# Messgeraet.net
KiCad netlist of a schematic drawn in EAGLE
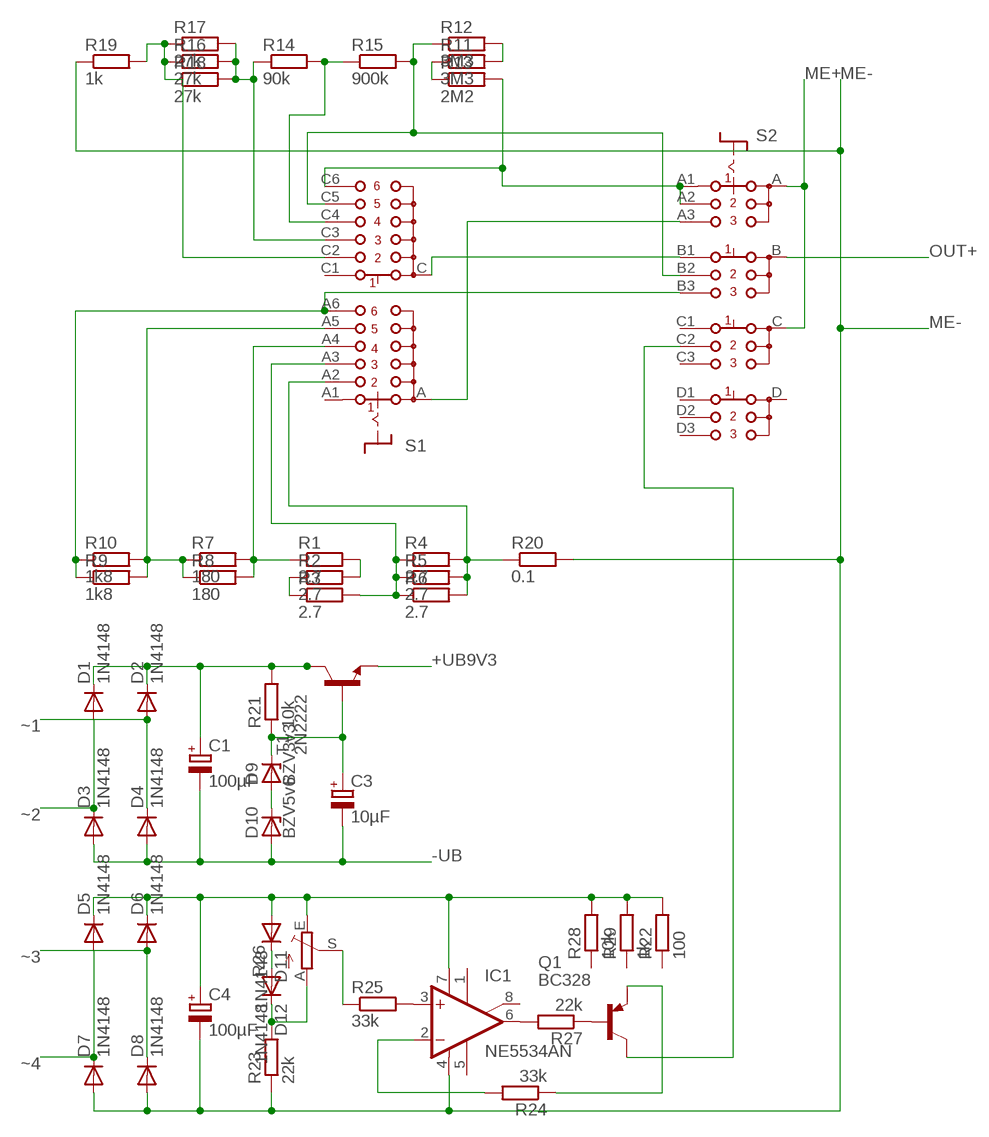
[diagram p0: schematic, sheet 1]

(export (version "E")
  (design (tool "Eeschema 10.0.6"))
  (components
    (comp (ref "C1")
      (value "100µF")
      (footprint "eagle-import:E5-10,5")
      (libsource (lib "eagle-import") (part "CPOL-EUE5-10.5"))
    )
    (comp (ref "C3")
      (value "10µF")
      (footprint "eagle-import:E5-10,5")
      (libsource (lib "eagle-import") (part "CPOL-EUE5-10.5"))
    )
    (comp (ref "C4")
      (value "100µF")
      (footprint "eagle-import:E5-10,5")
      (libsource (lib "eagle-import") (part "CPOL-EUE5-10.5"))
    )
    (comp (ref "D1")
      (value "1N4148")
      (footprint "eagle-import:DO35-7")
      (libsource (lib "eagle-import") (part "1N4148DO35-7"))
    )
    (comp (ref "D2")
      (value "1N4148")
      (footprint "eagle-import:DO35-7")
      (libsource (lib "eagle-import") (part "1N4148DO35-7"))
    )
    (comp (ref "D3")
      (value "1N4148")
      (footprint "eagle-import:DO35-7")
      (libsource (lib "eagle-import") (part "1N4148DO35-7"))
    )
    (comp (ref "D4")
      (value "1N4148")
      (footprint "eagle-import:DO35-7")
      (libsource (lib "eagle-import") (part "1N4148DO35-7"))
    )
    (comp (ref "D5")
      (value "1N4148")
      (footprint "eagle-import:DO35-7")
      (libsource (lib "eagle-import") (part "1N4148DO35-7"))
    )
    (comp (ref "D6")
      (value "1N4148")
      (footprint "eagle-import:DO35-7")
      (libsource (lib "eagle-import") (part "1N4148DO35-7"))
    )
    (comp (ref "D7")
      (value "1N4148")
      (footprint "eagle-import:DO35-7")
      (libsource (lib "eagle-import") (part "1N4148DO35-7"))
    )
    (comp (ref "D8")
      (value "1N4148")
      (footprint "eagle-import:DO35-7")
      (libsource (lib "eagle-import") (part "1N4148DO35-7"))
    )
    (comp (ref "D9")
      (value "BZV3v3")
      (footprint "eagle-import:DO34Z7")
      (libsource (lib "eagle-import") (part "BZV10"))
    )
    (comp (ref "D10")
      (value "BZV5v6")
      (footprint "eagle-import:DO34Z7")
      (libsource (lib "eagle-import") (part "BZV10"))
    )
    (comp (ref "D11")
      (value "1N4148")
      (footprint "eagle-import:DO35-7")
      (libsource (lib "eagle-import") (part "1N4148DO35-7"))
    )
    (comp (ref "D12")
      (value "1N4148")
      (footprint "eagle-import:DO35-7")
      (libsource (lib "eagle-import") (part "1N4148DO35-7"))
    )
    (comp (ref "IC1")
      (value "NE5534AN")
      (footprint "eagle-import:DIL08")
      (libsource (lib "eagle-import") (part "NE5534NA"))
    )
    (comp (ref "Q1")
      (value "BC328")
      (footprint "eagle-import:TO92-EBC")
      (libsource (lib "eagle-import") (part "BC328"))
    )
    (comp (ref "R1")
      (value "2.7")
      (footprint "eagle-import:0617_17")
      (libsource (lib "eagle-import") (part "resistor_R-EU_0617/17"))
    )
    (comp (ref "R2")
      (value "2.7")
      (footprint "eagle-import:0617_17")
      (libsource (lib "eagle-import") (part "resistor_R-EU_0617/17"))
    )
    (comp (ref "R3")
      (value "2.7")
      (footprint "eagle-import:0617_17")
      (libsource (lib "eagle-import") (part "resistor_R-EU_0617/17"))
    )
    (comp (ref "R4")
      (value "2.7")
      (footprint "eagle-import:0617_17")
      (libsource (lib "eagle-import") (part "resistor_R-EU_0617/17"))
    )
    (comp (ref "R5")
      (value "2.7")
      (footprint "eagle-import:0617_17")
      (libsource (lib "eagle-import") (part "resistor_R-EU_0617/17"))
    )
    (comp (ref "R6")
      (value "2.7")
      (footprint "eagle-import:0617_17")
      (libsource (lib "eagle-import") (part "resistor_R-EU_0617/17"))
    )
    (comp (ref "R7")
      (value "180")
      (footprint "eagle-import:0309_12")
      (libsource (lib "eagle-import") (part "resistor_R-EU_0309/12"))
    )
    (comp (ref "R8")
      (value "180")
      (footprint "eagle-import:0309_12")
      (libsource (lib "eagle-import") (part "resistor_R-EU_0309/12"))
    )
    (comp (ref "R9")
      (value "1k8")
      (footprint "eagle-import:0309_10")
      (libsource (lib "eagle-import") (part "resistor_R-EU_0309/10"))
    )
    (comp (ref "R10")
      (value "1k8")
      (footprint "eagle-import:0309_10")
      (libsource (lib "eagle-import") (part "resistor_R-EU_0309/10"))
    )
    (comp (ref "R11")
      (value "3M3")
      (footprint "eagle-import:0309_12")
      (libsource (lib "eagle-import") (part "resistor_R-EU_0309/12"))
    )
    (comp (ref "R12")
      (value "3M3")
      (footprint "eagle-import:0309_12")
      (libsource (lib "eagle-import") (part "resistor_R-EU_0309/12"))
    )
    (comp (ref "R13")
      (value "2M2")
      (footprint "eagle-import:0411_15")
      (libsource (lib "eagle-import") (part "resistor_R-EU_0411/15"))
    )
    (comp (ref "R14")
      (value "90k")
      (footprint "eagle-import:0411_15")
      (libsource (lib "eagle-import") (part "resistor_R-EU_0411/15"))
    )
    (comp (ref "R15")
      (value "900k")
      (footprint "eagle-import:0309V")
      (libsource (lib "eagle-import") (part "resistor_R-EU_0309/V"))
    )
    (comp (ref "R16")
      (value "27k")
      (footprint "eagle-import:0309_12")
      (libsource (lib "eagle-import") (part "resistor_R-EU_0309/12"))
    )
    (comp (ref "R17")
      (value "27k")
      (footprint "eagle-import:0309_12")
      (libsource (lib "eagle-import") (part "resistor_R-EU_0309/12"))
    )
    (comp (ref "R18")
      (value "27k")
      (footprint "eagle-import:0309_12")
      (libsource (lib "eagle-import") (part "resistor_R-EU_0309/12"))
    )
    (comp (ref "R19")
      (value "1k")
      (footprint "eagle-import:0309_10")
      (libsource (lib "eagle-import") (part "resistor_R-EU_0309/10"))
    )
    (comp (ref "R20")
      (value "0.1")
      (footprint "eagle-import:VTA52")
      (libsource (lib "eagle-import") (part "R-EU_VTA52"))
    )
    (comp (ref "R21")
      (value "10k")
      (footprint "eagle-import:0309_10")
      (libsource (lib "eagle-import") (part "resistor_R-EU_0309/10"))
    )
    (comp (ref "R22")
      (value "100")
      (footprint "eagle-import:0309_10")
      (libsource (lib "eagle-import") (part "resistor_R-EU_0309/10"))
    )
    (comp (ref "R23")
      (value "22k")
      (footprint "eagle-import:0309_10")
      (libsource (lib "eagle-import") (part "resistor_R-EU_0309/10"))
    )
    (comp (ref "R24")
      (value "33k")
      (footprint "eagle-import:0309_10")
      (libsource (lib "eagle-import") (part "resistor_R-EU_0309/10"))
    )
    (comp (ref "R25")
      (value "33k")
      (footprint "eagle-import:0309_10")
      (libsource (lib "eagle-import") (part "resistor_R-EU_0309/10"))
    )
    (comp (ref "R26")
      (value "TRIM_EU-RJ9W")
      (footprint "eagle-import:RJ9W")
      (libsource (lib "eagle-import") (part "TRIM_EU-RJ9W"))
    )
    (comp (ref "R27")
      (value "22k")
      (footprint "eagle-import:0309_10")
      (libsource (lib "eagle-import") (part "resistor_R-EU_0309/10"))
    )
    (comp (ref "R28")
      (value "10k")
      (footprint "eagle-import:0309_10")
      (libsource (lib "eagle-import") (part "resistor_R-EU_0309/10"))
    )
    (comp (ref "R29")
      (value "1k")
      (footprint "eagle-import:0309_10")
      (libsource (lib "eagle-import") (part "resistor_R-EU_0309/10"))
    )
    (comp (ref "S1")
      (value "CK102X06")
      (footprint "eagle-import:CK102X06")
      (libsource (lib "eagle-import") (part "CK102X06"))
    )
    (comp (ref "S2")
      (value "CK104X03")
      (footprint "eagle-import:CK104X03")
      (libsource (lib "eagle-import") (part "CK104X03"))
    )
    (comp (ref "T1")
      (value "2N2222")
      (footprint "eagle-import:TO18")
      (libsource (lib "eagle-import") (part "2N2222"))
    )
  )
  (nets
    (net (code "1") (name "/+UB9V3") (class "Default")
      (node (ref "T1") (pin "1") (pinfunction "E_1") (pintype "passive"))
    )
    (net (code "2") (name "/-UB") (class "Default")
      (node (ref "C1") (pin "-") (pinfunction "-_-") (pintype "passive"))
      (node (ref "C3") (pin "-") (pinfunction "-_-") (pintype "passive"))
      (node (ref "D10") (pin "A") (pinfunction "A_A") (pintype "passive"))
      (node (ref "D3") (pin "A") (pinfunction "A_A") (pintype "passive"))
      (node (ref "D4") (pin "A") (pinfunction "A_A") (pintype "passive"))
    )
    (net (code "3") (name "/ME+") (class "Default")
      (node (ref "S2") (pin "A") (pinfunction "A_A") (pintype "passive"))
      (node (ref "S2") (pin "C") (pinfunction "C_C") (pintype "passive"))
    )
    (net (code "4") (name "/ME-") (class "Default")
      (node (ref "C4") (pin "-") (pinfunction "-_-") (pintype "passive"))
      (node (ref "D7") (pin "A") (pinfunction "A_A") (pintype "passive"))
      (node (ref "D8") (pin "A") (pinfunction "A_A") (pintype "passive"))
      (node (ref "IC1") (pin "4") (pinfunction "V-_4") (pintype "power_in"))
      (node (ref "R19") (pin "1") (pinfunction "1_1") (pintype "passive"))
      (node (ref "R20") (pin "2") (pinfunction "2_2") (pintype "passive"))
      (node (ref "R23") (pin "1") (pinfunction "1_1") (pintype "passive"))
    )
    (net (code "5") (name "/OUT+") (class "Default")
      (node (ref "S2") (pin "B") (pinfunction "B_B") (pintype "passive"))
    )
    (net (code "6") (name "/~{1}") (class "Default")
      (node (ref "D2") (pin "A") (pinfunction "A_A") (pintype "passive"))
      (node (ref "D4") (pin "C") (pinfunction "C_C") (pintype "passive"))
    )
    (net (code "7") (name "/~{2}") (class "Default")
      (node (ref "D1") (pin "A") (pinfunction "A_A") (pintype "passive"))
      (node (ref "D3") (pin "C") (pinfunction "C_C") (pintype "passive"))
    )
    (net (code "8") (name "/~{3}") (class "Default")
      (node (ref "D6") (pin "A") (pinfunction "A_A") (pintype "passive"))
      (node (ref "D8") (pin "C") (pinfunction "C_C") (pintype "passive"))
    )
    (net (code "9") (name "/~{4}") (class "Default")
      (node (ref "D5") (pin "A") (pinfunction "A_A") (pintype "passive"))
      (node (ref "D7") (pin "C") (pinfunction "C_C") (pintype "passive"))
    )
    (net (code "10") (name "Net-(D10-PadC)") (class "Default")
      (node (ref "D10") (pin "C") (pinfunction "C_C") (pintype "passive"))
      (node (ref "D9") (pin "A") (pinfunction "A_A") (pintype "passive"))
    )
    (net (code "11") (name "Net-(D11-PadC)") (class "Default")
      (node (ref "D11") (pin "C") (pinfunction "C_C") (pintype "passive"))
      (node (ref "D12") (pin "A") (pinfunction "A_A") (pintype "passive"))
    )
    (net (code "12") (name "Net-(D12-PadC)") (class "Default")
      (node (ref "D12") (pin "C") (pinfunction "C_C") (pintype "passive"))
      (node (ref "R23") (pin "2") (pinfunction "2_2") (pintype "passive"))
      (node (ref "R26") (pin "A") (pinfunction "A_A") (pintype "passive"))
    )
    (net (code "13") (name "Net-(IC1-+IN)") (class "Default")
      (node (ref "IC1") (pin "3") (pinfunction "+IN_3") (pintype "input"))
      (node (ref "R25") (pin "2") (pinfunction "2_2") (pintype "passive"))
    )
    (net (code "14") (name "Net-(IC1--IN)") (class "Default")
      (node (ref "IC1") (pin "2") (pinfunction "-IN_2") (pintype "input"))
      (node (ref "R24") (pin "2") (pinfunction "2_2") (pintype "passive"))
    )
    (net (code "15") (name "Net-(IC1-OUT)") (class "Default")
      (node (ref "IC1") (pin "6") (pinfunction "OUT_6") (pintype "output"))
      (node (ref "R27") (pin "2") (pinfunction "2_2") (pintype "passive"))
    )
    (net (code "16") (name "Net-(IC1-V+)") (class "Default")
      (node (ref "C4") (pin "+") (pinfunction "+_+") (pintype "passive"))
      (node (ref "D11") (pin "A") (pinfunction "A_A") (pintype "passive"))
      (node (ref "D5") (pin "C") (pinfunction "C_C") (pintype "passive"))
      (node (ref "D6") (pin "C") (pinfunction "C_C") (pintype "passive"))
      (node (ref "IC1") (pin "7") (pinfunction "V+_7") (pintype "power_in"))
      (node (ref "R22") (pin "2") (pinfunction "2_2") (pintype "passive"))
      (node (ref "R26") (pin "E") (pinfunction "E_E") (pintype "passive"))
      (node (ref "R28") (pin "2") (pinfunction "2_2") (pintype "passive"))
      (node (ref "R29") (pin "2") (pinfunction "2_2") (pintype "passive"))
    )
    (net (code "17") (name "Net-(Q1-PadB)") (class "Default")
      (node (ref "Q1") (pin "B") (pinfunction "B_B") (pintype "passive"))
      (node (ref "R27") (pin "1") (pinfunction "1_1") (pintype "passive"))
    )
    (net (code "18") (name "Net-(Q1-PadC)") (class "Default")
      (node (ref "Q1") (pin "C") (pinfunction "C_C") (pintype "passive"))
      (node (ref "S2") (pin "C2") (pinfunction "C2_C2") (pintype "passive"))
    )
    (net (code "19") (name "Net-(Q1-PadE)") (class "Default")
      (node (ref "Q1") (pin "E") (pinfunction "E_E") (pintype "passive"))
      (node (ref "R24") (pin "1") (pinfunction "1_1") (pintype "passive"))
    )
    (net (code "20") (name "Net-(R1-Pad1)") (class "Default")
      (node (ref "R1") (pin "1") (pinfunction "1_1") (pintype "passive"))
      (node (ref "R7") (pin "2") (pinfunction "2_2") (pintype "passive"))
      (node (ref "R8") (pin "2") (pinfunction "2_2") (pintype "passive"))
      (node (ref "S1") (pin "A4") (pinfunction "A4_A4") (pintype "passive"))
    )
    (net (code "21") (name "Net-(R1-Pad2)") (class "Default")
      (node (ref "R1") (pin "2") (pinfunction "2_2") (pintype "passive"))
      (node (ref "R2") (pin "2") (pinfunction "2_2") (pintype "passive"))
    )
    (net (code "22") (name "Net-(R2-Pad1)") (class "Default")
      (node (ref "R2") (pin "1") (pinfunction "1_1") (pintype "passive"))
      (node (ref "R3") (pin "1") (pinfunction "1_1") (pintype "passive"))
    )
    (net (code "23") (name "Net-(R3-Pad2)") (class "Default")
      (node (ref "R3") (pin "2") (pinfunction "2_2") (pintype "passive"))
      (node (ref "R4") (pin "1") (pinfunction "1_1") (pintype "passive"))
      (node (ref "R5") (pin "1") (pinfunction "1_1") (pintype "passive"))
      (node (ref "R6") (pin "1") (pinfunction "1_1") (pintype "passive"))
      (node (ref "S1") (pin "A3") (pinfunction "A3_A3") (pintype "passive"))
    )
    (net (code "24") (name "Net-(R10-Pad1)") (class "Default")
      (node (ref "R10") (pin "1") (pinfunction "1_1") (pintype "passive"))
      (node (ref "R9") (pin "1") (pinfunction "1_1") (pintype "passive"))
      (node (ref "S1") (pin "A6") (pinfunction "A6_A6") (pintype "passive"))
      (node (ref "S2") (pin "B3") (pinfunction "B3_B3") (pintype "passive"))
    )
    (net (code "25") (name "Net-(R10-Pad2)") (class "Default")
      (node (ref "R10") (pin "2") (pinfunction "2_2") (pintype "passive"))
      (node (ref "R7") (pin "1") (pinfunction "1_1") (pintype "passive"))
      (node (ref "R8") (pin "1") (pinfunction "1_1") (pintype "passive"))
      (node (ref "R9") (pin "2") (pinfunction "2_2") (pintype "passive"))
      (node (ref "S1") (pin "A5") (pinfunction "A5_A5") (pintype "passive"))
    )
    (net (code "26") (name "Net-(R11-Pad1)") (class "Default")
      (node (ref "R11") (pin "1") (pinfunction "1_1") (pintype "passive"))
      (node (ref "R13") (pin "1") (pinfunction "1_1") (pintype "passive"))
    )
    (net (code "27") (name "Net-(R11-Pad2)") (class "Default")
      (node (ref "R11") (pin "2") (pinfunction "2_2") (pintype "passive"))
      (node (ref "R12") (pin "2") (pinfunction "2_2") (pintype "passive"))
    )
    (net (code "28") (name "Net-(R12-Pad1)") (class "Default")
      (node (ref "R12") (pin "1") (pinfunction "1_1") (pintype "passive"))
      (node (ref "R15") (pin "2") (pinfunction "2_2") (pintype "passive"))
      (node (ref "S1") (pin "C5") (pinfunction "C5_C5") (pintype "passive"))
      (node (ref "S2") (pin "B2") (pinfunction "B2_B2") (pintype "passive"))
    )
    (net (code "29") (name "Net-(R13-Pad2)") (class "Default")
      (node (ref "R13") (pin "2") (pinfunction "2_2") (pintype "passive"))
      (node (ref "S1") (pin "C6") (pinfunction "C6_C6") (pintype "passive"))
      (node (ref "S2") (pin "A1") (pinfunction "A1_A1") (pintype "passive"))
      (node (ref "S2") (pin "A2") (pinfunction "A2_A2") (pintype "passive"))
    )
    (net (code "30") (name "Net-(R14-Pad1)") (class "Default")
      (node (ref "R14") (pin "1") (pinfunction "1_1") (pintype "passive"))
      (node (ref "R16") (pin "2") (pinfunction "2_2") (pintype "passive"))
      (node (ref "R17") (pin "2") (pinfunction "2_2") (pintype "passive"))
      (node (ref "R18") (pin "2") (pinfunction "2_2") (pintype "passive"))
      (node (ref "S1") (pin "C3") (pinfunction "C3_C3") (pintype "passive"))
    )
    (net (code "31") (name "Net-(R14-Pad2)") (class "Default")
      (node (ref "R14") (pin "2") (pinfunction "2_2") (pintype "passive"))
      (node (ref "R15") (pin "1") (pinfunction "1_1") (pintype "passive"))
      (node (ref "S1") (pin "C4") (pinfunction "C4_C4") (pintype "passive"))
    )
    (net (code "32") (name "Net-(R16-Pad1)") (class "Default")
      (node (ref "R16") (pin "1") (pinfunction "1_1") (pintype "passive"))
      (node (ref "R17") (pin "1") (pinfunction "1_1") (pintype "passive"))
      (node (ref "R18") (pin "1") (pinfunction "1_1") (pintype "passive"))
      (node (ref "R19") (pin "2") (pinfunction "2_2") (pintype "passive"))
      (node (ref "S1") (pin "C2") (pinfunction "C2_C2") (pintype "passive"))
    )
    (net (code "33") (name "Net-(R20-Pad1)") (class "Default")
      (node (ref "R20") (pin "1") (pinfunction "1_1") (pintype "passive"))
      (node (ref "R4") (pin "2") (pinfunction "2_2") (pintype "passive"))
      (node (ref "R5") (pin "2") (pinfunction "2_2") (pintype "passive"))
      (node (ref "R6") (pin "2") (pinfunction "2_2") (pintype "passive"))
      (node (ref "S1") (pin "A2") (pinfunction "A2_A2") (pintype "passive"))
    )
    (net (code "34") (name "Net-(R25-Pad1)") (class "Default")
      (node (ref "R25") (pin "1") (pinfunction "1_1") (pintype "passive"))
      (node (ref "R26") (pin "S") (pinfunction "S_S") (pintype "passive"))
    )
    (net (code "35") (name "Net-(S1-PadA)") (class "Default")
      (node (ref "S1") (pin "A") (pinfunction "A_A") (pintype "passive"))
      (node (ref "S2") (pin "A3") (pinfunction "A3_A3") (pintype "passive"))
    )
    (net (code "36") (name "Net-(S1-PadC)") (class "Default")
      (node (ref "S1") (pin "C") (pinfunction "C_C") (pintype "passive"))
      (node (ref "S2") (pin "B1") (pinfunction "B1_B1") (pintype "passive"))
    )
    (net (code "37") (name "Net-(T1-B)") (class "Default")
      (node (ref "C3") (pin "+") (pinfunction "+_+") (pintype "passive"))
      (node (ref "D9") (pin "C") (pinfunction "C_C") (pintype "passive"))
      (node (ref "R21") (pin "1") (pinfunction "1_1") (pintype "passive"))
      (node (ref "T1") (pin "2") (pinfunction "B_2") (pintype "passive"))
    )
    (net (code "38") (name "Net-(T1-C)") (class "Default")
      (node (ref "C1") (pin "+") (pinfunction "+_+") (pintype "passive"))
      (node (ref "D1") (pin "C") (pinfunction "C_C") (pintype "passive"))
      (node (ref "D2") (pin "C") (pinfunction "C_C") (pintype "passive"))
      (node (ref "R21") (pin "2") (pinfunction "2_2") (pintype "passive"))
      (node (ref "T1") (pin "3") (pinfunction "C_3") (pintype "passive"))
    )
    (net (code "39") (name "unconnected-(IC1-CMP-Pad5)") (class "Default")
      (node (ref "IC1") (pin "5") (pinfunction "CMP_5") (pintype "passive"))
    )
    (net (code "40") (name "unconnected-(IC1-ON-Pad1)") (class "Default")
      (node (ref "IC1") (pin "1") (pinfunction "ON_1") (pintype "passive"))
    )
    (net (code "41") (name "unconnected-(IC1-ON{slash}CMP-Pad8)") (class "Default")
      (node (ref "IC1") (pin "8") (pinfunction "ON/CMP_8") (pintype "passive"))
    )
    (net (code "42") (name "unconnected-(R22-Pad1)") (class "Default")
      (node (ref "R22") (pin "1") (pinfunction "1_1") (pintype "passive"))
    )
    (net (code "43") (name "unconnected-(R28-Pad1)") (class "Default")
      (node (ref "R28") (pin "1") (pinfunction "1_1") (pintype "passive"))
    )
    (net (code "44") (name "unconnected-(R29-Pad1)") (class "Default")
      (node (ref "R29") (pin "1") (pinfunction "1_1") (pintype "passive"))
    )
    (net (code "45") (name "unconnected-(S1-PadA1)") (class "Default")
      (node (ref "S1") (pin "A1") (pinfunction "A1_A1") (pintype "passive"))
    )
    (net (code "46") (name "unconnected-(S1-PadC1)") (class "Default")
      (node (ref "S1") (pin "C1") (pinfunction "C1_C1") (pintype "passive"))
    )
    (net (code "47") (name "unconnected-(S2-PadC1)") (class "Default")
      (node (ref "S2") (pin "C1") (pinfunction "C1_C1") (pintype "passive"))
    )
    (net (code "48") (name "unconnected-(S2-PadC3)") (class "Default")
      (node (ref "S2") (pin "C3") (pinfunction "C3_C3") (pintype "passive"))
    )
    (net (code "49") (name "unconnected-(S2-PadD)") (class "Default")
      (node (ref "S2") (pin "D") (pinfunction "D_D") (pintype "passive"))
    )
    (net (code "50") (name "unconnected-(S2-PadD1)") (class "Default")
      (node (ref "S2") (pin "D1") (pinfunction "D1_D1") (pintype "passive"))
    )
    (net (code "51") (name "unconnected-(S2-PadD2)") (class "Default")
      (node (ref "S2") (pin "D2") (pinfunction "D2_D2") (pintype "passive"))
    )
    (net (code "52") (name "unconnected-(S2-PadD3)") (class "Default")
      (node (ref "S2") (pin "D3") (pinfunction "D3_D3") (pintype "passive"))
    )
  )
)
